# main.net
KiCad netlist of a schematic drawn in Altium Designer
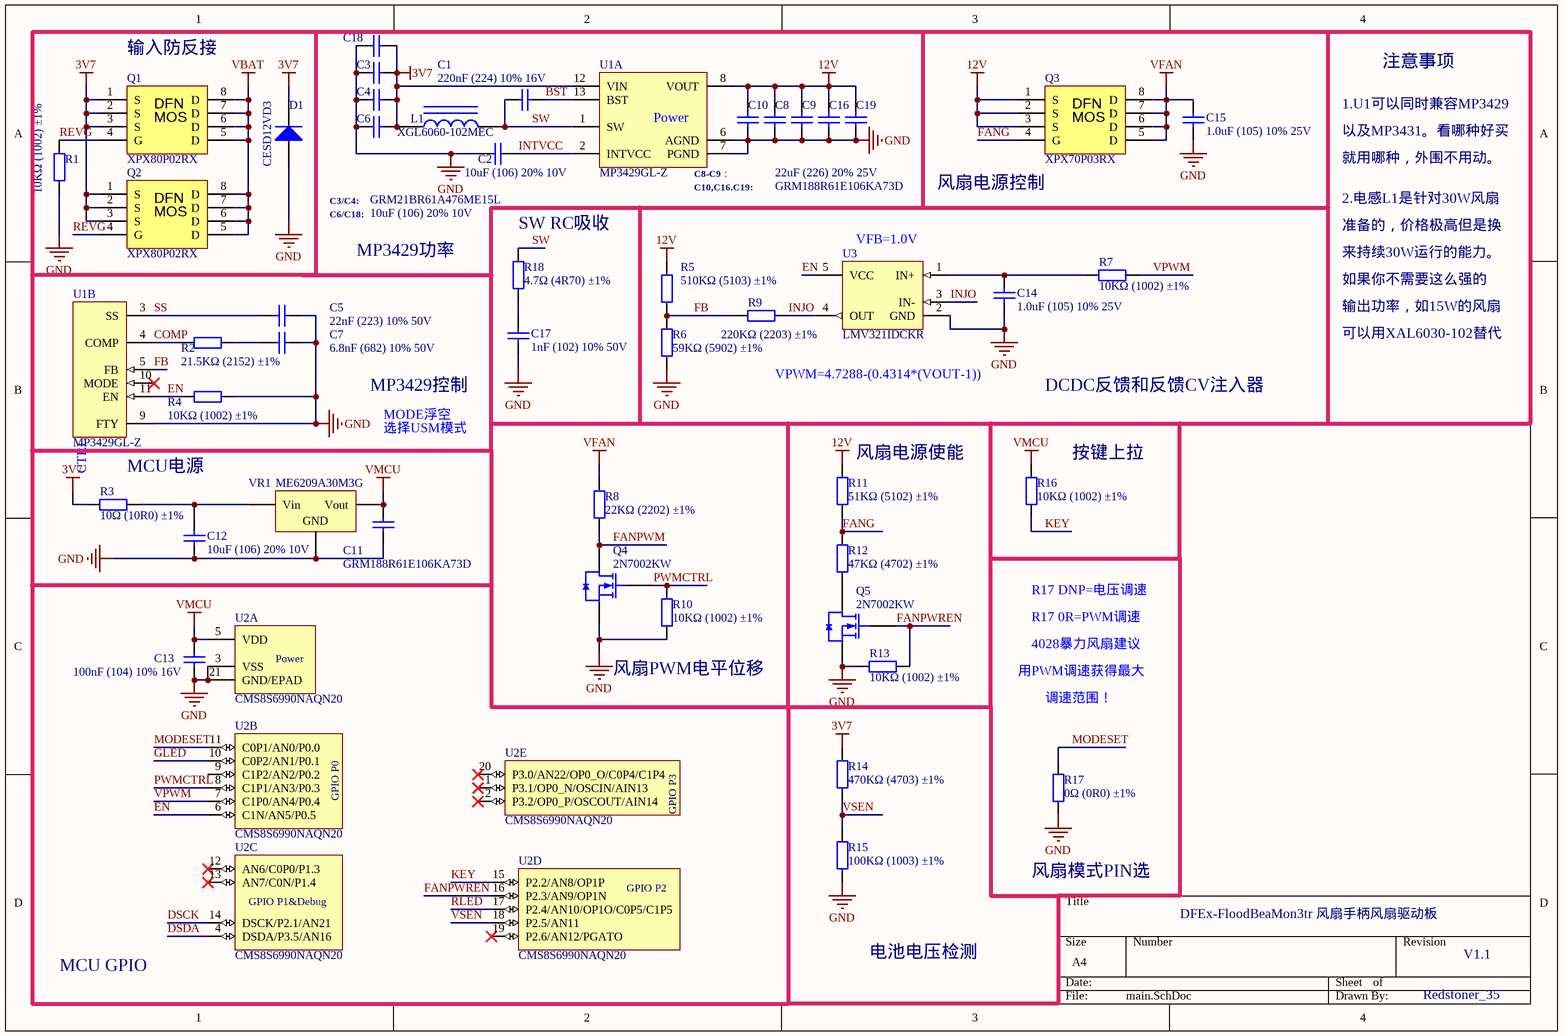
[diagram p0: main.SchDoc]

(export (version "E")
  (design (tool "Eeschema 10.0.6"))
  (components
    (comp (ref "C1")
      (value "220nF (224) 10% 16V")
      (footprint "0402_C")
      (description "贴片电容")
      (libsource (lib "Miscellaneous Devices LC") (part "0402 220nF (224) 10% 16V"))
    )
    (comp (ref "C2")
      (value "10uF (106) 20% 10V")
      (footprint "0402_C")
      (description "贴片电容")
      (libsource (lib "Miscellaneous Devices LC") (part "0402 10uF (106) 20% 6.3V"))
    )
    (comp (ref "C3")
      (value "GRM21BR61A476ME15L")
      (footprint "0805_C")
      (description "贴片MLCC电容，47uF (476) 20% 10V")
      (libsource (lib "Miscellaneous Devices LC") (part "0805 22uF (226) 20% 25V"))
    )
    (comp (ref "C4")
      (value "GRM21BR61A476ME15L")
      (footprint "0805_C")
      (description "贴片MLCC电容，47uF (476) 20% 10V")
      (libsource (lib "Miscellaneous Devices LC") (part "0805 22uF (226) 20% 25V"))
    )
    (comp (ref "C5")
      (value "22nF (223) 10% 50V")
      (footprint "0402_C")
      (description "贴片电容")
      (libsource (lib "Miscellaneous Devices LC") (part "0402 22nF (223) 10% 50V"))
    )
    (comp (ref "C6")
      (value "10uF (106) 20% 10V")
      (footprint "0402_C")
      (description "贴片电容")
      (libsource (lib "Miscellaneous Devices LC") (part "0402 10uF (106) 20% 6.3V"))
    )
    (comp (ref "C7")
      (value "6.8nF (682) 10% 50V")
      (footprint "0402_C")
      (description "贴片电容")
      (libsource (lib "Miscellaneous Devices LC") (part "0402 10nF (103) 10% 50V"))
    )
    (comp (ref "C8")
      (value "22uF (226) 20% 25V")
      (footprint "0805_C")
      (description "贴片电容")
      (libsource (lib "Miscellaneous Devices LC") (part "0805 22uF (226) 20% 25V"))
    )
    (comp (ref "C9")
      (value "22uF (226) 20% 25V")
      (footprint "0805_C")
      (description "贴片电容")
      (libsource (lib "Miscellaneous Devices LC") (part "0805 22uF (226) 20% 25V"))
    )
    (comp (ref "C10")
      (value "GRM188R61E106KA73D")
      (footprint "0603_C")
      (description "0603贴片MLCC电容 10uF ±20% 25V X5R")
      (libsource (lib "Miscellaneous Devices LC") (part "0603 4.7uF (475) 10% 16V"))
    )
    (comp (ref "C11")
      (value "GRM188R61E106KA73D")
      (footprint "0603_C")
      (description "0603贴片MLCC电容 10uF ±20% 25V X5R")
      (libsource (lib "Miscellaneous Devices LC") (part "0603 10uF (106) 10% 10V"))
    )
    (comp (ref "C12")
      (value "10uF (106) 20% 10V")
      (footprint "0402_C")
      (description "贴片电容")
      (libsource (lib "Miscellaneous Devices LC") (part "0402 10uF (106) 20% 6.3V"))
    )
    (comp (ref "C13")
      (value "100nF (104) 10% 16V")
      (footprint "0402_C")
      (description "贴片电容")
      (libsource (lib "Miscellaneous Devices LC") (part "0402 100nF (104) 10% 16V"))
    )
    (comp (ref "C14")
      (value "1.0uF (105) 10% 25V")
      (footprint "0402_C")
      (description "贴片电容")
      (libsource (lib "Miscellaneous Devices LC") (part "0402 1.0uF (105) 10% 25V"))
    )
    (comp (ref "C15")
      (value "1.0uF (105) 10% 25V")
      (footprint "0402_C")
      (description "贴片电容")
      (libsource (lib "Miscellaneous Devices LC") (part "0402 1.0uF (105) 10% 25V"))
    )
    (comp (ref "C16")
      (value "GRM188R61E106KA73D")
      (footprint "0603_C")
      (description "0603贴片MLCC电容 10uF ±20% 25V X5R")
      (libsource (lib "Miscellaneous Devices LC") (part "0603 4.7uF (475) 10% 16V"))
    )
    (comp (ref "C17")
      (value "1nF (102) 10% 50V")
      (footprint "0402_C")
      (description "贴片电容")
      (libsource (lib "Miscellaneous Devices LC") (part "0402 1nF (102) 10% 50V"))
    )
    (comp (ref "C18")
      (value "10uF (106) 20% 10V")
      (footprint "0402_C")
      (description "贴片电容")
      (libsource (lib "Miscellaneous Devices LC") (part "0402 10uF (106) 20% 6.3V"))
    )
    (comp (ref "C19")
      (value "GRM188R61E106KA73D")
      (footprint "0603_C")
      (description "0603贴片MLCC电容 10uF ±20% 25V X5R")
      (libsource (lib "Miscellaneous Devices LC") (part "0603 4.7uF (475) 10% 16V"))
    )
    (comp (ref "D1")
      (value "CESD12VD3")
      (footprint "SOD-323")
      (description "12V TVS二极管")
      (libsource (lib "Miscellaneous Devices LC") (part "SOD-323 1N4148WS T4"))
    )
    (comp (ref "L1")
      (value "XGL6060-102MEC")
      (footprint "XAL6030-xxxME")
      (description "线艺超低损耗系列一体成型电感 1.0uH±20% 2.5mΩ DCR 23A饱和电流 6.5*6.7*6.2mm")
      (fields (field (name "PUBLISHER") "Altium Limited"))
      (libsource (lib "Miscellaneous Devices") (part "Inductor Iron"))
    )
    (comp (ref "Q1")
      (value "XPX80P02RX")
      (footprint "DFN-8_L3.0-W3.0-P0.65-BL")
      (description "-20V -80A 4mR内阻 P沟道MOSFET")
      (libsource (lib "custom") (part "SON/DFN5x6 MOS"))
    )
    (comp (ref "Q2")
      (value "XPX80P02RX")
      (footprint "DFN-8_L3.0-W3.0-P0.65-BL")
      (description "-20V -80A 4mR内阻 P沟道MOSFET")
      (libsource (lib "custom") (part "SON/DFN5x6 MOS"))
    )
    (comp (ref "Q3")
      (value "XPX70P03RX")
      (footprint "DFN-8_L3.0-W3.0-P0.65-BL")
      (description "-30V -70A 6.5mR P沟道增强型MOSFET")
      (libsource (lib "custom") (part "SON/DFN5x6 MOS"))
    )
    (comp (ref "Q4")
      (value "2N7002KW")
      (footprint "SC70-3")
      (description "单N沟道MOSFET(场效应管)")
      (libsource (lib "Miscellaneous Devices LC") (part "2N7002 7002"))
    )
    (comp (ref "Q5")
      (value "2N7002KW")
      (footprint "SC70-3")
      (description "单N沟道MOSFET(场效应管)")
      (libsource (lib "Miscellaneous Devices LC") (part "2N7002 7002"))
    )
    (comp (ref "R1")
      (value "10KΩ (1002) ±1%")
      (footprint "0402_R")
      (description "贴片电阻")
      (libsource (lib "") (part "0402 10KΩ (1002) 1%_1"))
    )
    (comp (ref "R2")
      (value "21.5KΩ (2152) ±1%")
      (footprint "0402_R")
      (description "贴片电阻")
      (libsource (lib "Miscellaneous Devices LC") (part "0402 18KΩ (1802) 1%"))
    )
    (comp (ref "R3")
      (value "10Ω (10R0) ±1%")
      (footprint "0402_R")
      (description "贴片电阻")
      (libsource (lib "Miscellaneous Devices LC") (part "0402 22Ω (22R0) 1%"))
    )
    (comp (ref "R4")
      (value "10KΩ (1002) ±1%")
      (footprint "0402_R")
      (description "贴片电阻")
      (libsource (lib "Miscellaneous Devices LC") (part "0402 10KΩ (1002) 1%"))
    )
    (comp (ref "R5")
      (value "510KΩ (5103) ±1%")
      (footprint "0402_R")
      (description "贴片电阻")
      (libsource (lib "Miscellaneous Devices LC") (part "0402 510KΩ (5103) 1%"))
    )
    (comp (ref "R6")
      (value "59KΩ (5902) ±1%")
      (footprint "0402_R")
      (description "贴片电阻")
      (libsource (lib "Miscellaneous Devices LC") (part "0402 510KΩ (5103) 1%"))
    )
    (comp (ref "R7")
      (value "10KΩ (1002) ±1%")
      (footprint "0402_R")
      (description "贴片电阻")
      (libsource (lib "") (part "0402 10KΩ (1002) 1%_2"))
    )
    (comp (ref "R8")
      (value "22KΩ (2202) ±1%")
      (footprint "0402_R")
      (description "贴片电阻")
      (libsource (lib "Miscellaneous Devices LC") (part "0402 22KΩ (2202) 1%"))
    )
    (comp (ref "R9")
      (value "220KΩ (2203) ±1%")
      (footprint "0402_R")
      (description "贴片电阻")
      (libsource (lib "") (part "0402 100KΩ (1003) 1%_1"))
    )
    (comp (ref "R10")
      (value "10KΩ (1002) ±1%")
      (footprint "0402_R")
      (description "贴片电阻")
      (libsource (lib "") (part "0402 10KΩ (1002) 1%_1"))
    )
    (comp (ref "R11")
      (value "51KΩ (5102) ±1%")
      (footprint "0402_R")
      (description "贴片电阻")
      (libsource (lib "Miscellaneous Devices LC") (part "0402 47KΩ (4702) 1%"))
    )
    (comp (ref "R12")
      (value "47KΩ (4702) ±1%")
      (footprint "0402_R")
      (description "贴片电阻")
      (libsource (lib "Miscellaneous Devices LC") (part "0402 51KΩ (5102) 1%"))
    )
    (comp (ref "R13")
      (value "10KΩ (1002) ±1%")
      (footprint "0402_R")
      (description "贴片电阻")
      (libsource (lib "Miscellaneous Devices LC") (part "0402 10KΩ (1002) 1%"))
    )
    (comp (ref "R14")
      (value "470KΩ (4703) ±1%")
      (footprint "0402_R")
      (description "贴片电阻")
      (libsource (lib "Miscellaneous Devices LC") (part "0402 470KΩ (4703) 1%"))
    )
    (comp (ref "R15")
      (value "100KΩ (1003) ±1%")
      (footprint "0402_R")
      (description "贴片电阻")
      (libsource (lib "Miscellaneous Devices LC") (part "0402 100KΩ (1003) 1%"))
    )
    (comp (ref "R16")
      (value "10KΩ (1002) ±1%")
      (footprint "0402_R")
      (description "贴片电阻")
      (libsource (lib "") (part "0402 10KΩ (1002) 1%_1"))
    )
    (comp (ref "R17")
      (value "0Ω (0R0) ±1%")
      (footprint "0402_R")
      (description "贴片电阻")
      (libsource (lib "Miscellaneous Devices LC") (part "0402 0Ω (0R0) 1%"))
    )
    (comp (ref "R18")
      (value "4.7Ω (4R70) ±1%")
      (footprint "0402_R")
      (description "贴片电阻")
      (libsource (lib "Miscellaneous Devices LC") (part "0402 1Ω (1R00) 1%"))
    )
    (comp (ref "U1")
      (value "MP3429GL-Z")
      (footprint "QFN-MLP3*4-13L")
      (description "16VOUT, 21A Peak Current Fully Integrated Synchronous Boost Converter")
      (libsource (lib "") (part "MP3429GL-Z_1"))
    )
    (comp (ref "U2")
      (value "CMS8S6990NAQN20")
      (footprint "QFN40P300X300X800_HS-21N")
      (description "增强型闪存1T 8051单片机，16KB Flash 256+1K XRAM")
      (libsource (lib "custom") (part "CM8S6990NA-QFN20"))
    )
    (comp (ref "U3")
      (value "LMV321IDCKR")
      (footprint "SC70-5")
      (description "CMOS超小型运算放大器，SC70-5")
      (libsource (lib "custom") (part "LMV321IDCKR"))
    )
    (comp (ref "VR1")
      (value "ME6209A30M3G")
      (footprint "SOT-23-3L")
      (description "低压差线性稳压(LDO)，输入耐压18V 输出3V 300mA最大电流 SOT23-3封装")
      (libsource (lib "Miscellaneous Devices LC") (part "SOT-23 XC6206P332MR"))
    )
  )
  (nets
    (net (code "1") (name "/BST") (class "Default")
      (node (ref "C1") (pin "2") (pinfunction "2_2") (pintype "passive"))
      (node (ref "U1") (pin "13") (pinfunction "BST_13") (pintype "power_in"))
    )
    (net (code "2") (name "/COMP") (class "Default")
      (node (ref "R2") (pin "1") (pinfunction "1_1") (pintype "passive"))
      (node (ref "U1") (pin "4") (pinfunction "COMP_4") (pintype "passive"))
    )
    (net (code "3") (name "/DSCK") (class "Default")
      (node (ref "U2") (pin "14") (pinfunction "DSCK/P2.1/AN21_14") (pintype "bidirectional"))
    )
    (net (code "4") (name "/DSDA") (class "Default")
      (node (ref "U2") (pin "4") (pinfunction "DSDA/P3.5/AN16_4") (pintype "bidirectional"))
    )
    (net (code "5") (name "/EN") (class "Default")
      (node (ref "R4") (pin "2") (pinfunction "2_2") (pintype "passive"))
      (node (ref "U1") (pin "11") (pinfunction "EN_11") (pintype "input"))
      (node (ref "U2") (pin "6") (pinfunction "C1N/AN5/P0.5_6") (pintype "bidirectional"))
      (node (ref "U3") (pin "5") (pinfunction "VCC_5") (pintype "power_in"))
    )
    (net (code "6") (name "/FANG") (class "Default")
      (node (ref "Q3") (pin "4") (pinfunction "G_4") (pintype "passive"))
      (node (ref "R11") (pin "1") (pinfunction "1_1") (pintype "passive"))
      (node (ref "R12") (pin "2") (pinfunction "2_2") (pintype "passive"))
    )
    (net (code "7") (name "/FANPWM") (class "Default")
      (node (ref "Q4") (pin "3") (pinfunction "D_3") (pintype "passive"))
      (node (ref "R8") (pin "1") (pinfunction "1_1") (pintype "passive"))
    )
    (net (code "8") (name "/FANPWREN") (class "Default")
      (node (ref "Q5") (pin "1") (pinfunction "G_1") (pintype "passive"))
      (node (ref "R13") (pin "1") (pinfunction "1_1") (pintype "passive"))
      (node (ref "U2") (pin "16") (pinfunction "P2.3/AN9/OP1N_16") (pintype "bidirectional"))
    )
    (net (code "9") (name "/FB") (class "Default")
      (node (ref "R5") (pin "1") (pinfunction "1_1") (pintype "passive"))
      (node (ref "R6") (pin "2") (pinfunction "2_2") (pintype "passive"))
      (node (ref "R9") (pin "1") (pinfunction "1_1") (pintype "passive"))
      (node (ref "U1") (pin "5") (pinfunction "FB_5") (pintype "input"))
    )
    (net (code "10") (name "/GLED") (class "Default")
      (node (ref "U2") (pin "10") (pinfunction "C0P2/AN1/P0.1_10") (pintype "bidirectional"))
    )
    (net (code "11") (name "/INJO") (class "Default")
      (node (ref "R9") (pin "2") (pinfunction "2_2") (pintype "passive"))
      (node (ref "U3") (pin "3") (pinfunction "IN-_3") (pintype "input"))
      (node (ref "U3") (pin "4") (pinfunction "OUT_4") (pintype "output"))
    )
    (net (code "12") (name "/INTVCC") (class "Default")
      (node (ref "C2") (pin "2") (pinfunction "2_2") (pintype "passive"))
      (node (ref "U1") (pin "2") (pinfunction "INTVCC_2") (pintype "power_in"))
    )
    (net (code "13") (name "/KEY") (class "Default")
      (node (ref "R16") (pin "1") (pinfunction "1_1") (pintype "passive"))
      (node (ref "U2") (pin "15") (pinfunction "P2.2/AN8/OP1P_15") (pintype "bidirectional"))
    )
    (net (code "14") (name "/MODESET") (class "Default")
      (node (ref "R17") (pin "2") (pinfunction "2_2") (pintype "passive"))
      (node (ref "U2") (pin "11") (pinfunction "C0P1/AN0/P0.0_11") (pintype "bidirectional"))
    )
    (net (code "15") (name "/PWMCTRL") (class "Default")
      (node (ref "Q4") (pin "1") (pinfunction "G_1") (pintype "passive"))
      (node (ref "R10") (pin "2") (pinfunction "2_2") (pintype "passive"))
      (node (ref "U2") (pin "8") (pinfunction "C1P1/AN3/P0.3_8") (pintype "bidirectional"))
    )
    (net (code "16") (name "/REVG") (class "Default")
      (node (ref "Q1") (pin "4") (pinfunction "G_4") (pintype "passive"))
      (node (ref "Q2") (pin "4") (pinfunction "G_4") (pintype "passive"))
      (node (ref "R1") (pin "2") (pinfunction "2_2") (pintype "passive"))
    )
    (net (code "17") (name "/RLED") (class "Default")
      (node (ref "U2") (pin "17") (pinfunction "P2.4/AN10/OP1O/C0P5/C1P5_17") (pintype "bidirectional"))
    )
    (net (code "18") (name "/SS") (class "Default")
      (node (ref "C5") (pin "1") (pinfunction "1_1") (pintype "passive"))
      (node (ref "U1") (pin "3") (pinfunction "SS_3") (pintype "passive"))
    )
    (net (code "19") (name "/SW") (class "Default")
      (node (ref "C1") (pin "1") (pinfunction "1_1") (pintype "passive"))
      (node (ref "L1") (pin "2") (pinfunction "2_2") (pintype "passive"))
      (node (ref "R18") (pin "2") (pinfunction "2_2") (pintype "passive"))
      (node (ref "U1") (pin "1") (pinfunction "SW_1") (pintype "power_in"))
    )
    (net (code "20") (name "/VPWM") (class "Default")
      (node (ref "R7") (pin "2") (pinfunction "2_2") (pintype "passive"))
      (node (ref "U2") (pin "7") (pinfunction "C1P0/AN4/P0.4_7") (pintype "bidirectional"))
    )
    (net (code "21") (name "/VSEN") (class "Default")
      (node (ref "R14") (pin "1") (pinfunction "1_1") (pintype "passive"))
      (node (ref "R15") (pin "2") (pinfunction "2_2") (pintype "passive"))
      (node (ref "U2") (pin "18") (pinfunction "P2.5/AN11_18") (pintype "bidirectional"))
    )
    (net (code "22") (name "3V7") (class "Default")
      (node (ref "C18") (pin "2") (pinfunction "2_2") (pintype "passive"))
      (node (ref "C3") (pin "2") (pinfunction "2_2") (pintype "passive"))
      (node (ref "C4") (pin "2") (pinfunction "2_2") (pintype "passive"))
      (node (ref "C6") (pin "2") (pinfunction "2_2") (pintype "passive"))
      (node (ref "D1") (pin "2") (pinfunction "K_2") (pintype "passive"))
      (node (ref "L1") (pin "1") (pinfunction "1_1") (pintype "passive"))
      (node (ref "Q1") (pin "1") (pinfunction "S_1") (pintype "passive"))
      (node (ref "Q1") (pin "2") (pinfunction "S_2") (pintype "passive"))
      (node (ref "Q1") (pin "3") (pinfunction "S_3") (pintype "passive"))
      (node (ref "Q2") (pin "1") (pinfunction "S_1") (pintype "passive"))
      (node (ref "Q2") (pin "2") (pinfunction "S_2") (pintype "passive"))
      (node (ref "Q2") (pin "3") (pinfunction "S_3") (pintype "passive"))
      (node (ref "R14") (pin "2") (pinfunction "2_2") (pintype "passive"))
      (node (ref "R3") (pin "1") (pinfunction "1_1") (pintype "passive"))
      (node (ref "U1") (pin "12") (pinfunction "VIN_12") (pintype "power_in"))
    )
    (net (code "23") (name "12V") (class "Default")
      (node (ref "C10") (pin "2") (pinfunction "2_2") (pintype "passive"))
      (node (ref "C16") (pin "2") (pinfunction "2_2") (pintype "passive"))
      (node (ref "C19") (pin "2") (pinfunction "2_2") (pintype "passive"))
      (node (ref "C8") (pin "2") (pinfunction "2_2") (pintype "passive"))
      (node (ref "C9") (pin "2") (pinfunction "2_2") (pintype "passive"))
      (node (ref "Q3") (pin "1") (pinfunction "S_1") (pintype "passive"))
      (node (ref "Q3") (pin "2") (pinfunction "S_2") (pintype "passive"))
      (node (ref "Q3") (pin "3") (pinfunction "S_3") (pintype "passive"))
      (node (ref "R11") (pin "2") (pinfunction "2_2") (pintype "passive"))
      (node (ref "R5") (pin "2") (pinfunction "2_2") (pintype "passive"))
      (node (ref "U1") (pin "8") (pinfunction "VOUT_8") (pintype "power_in"))
    )
    (net (code "24") (name "GND") (class "Default")
      (node (ref "C10") (pin "1") (pinfunction "1_1") (pintype "passive"))
      (node (ref "C11") (pin "1") (pinfunction "1_1") (pintype "passive"))
      (node (ref "C12") (pin "1") (pinfunction "1_1") (pintype "passive"))
      (node (ref "C13") (pin "1") (pinfunction "1_1") (pintype "passive"))
      (node (ref "C14") (pin "1") (pinfunction "1_1") (pintype "passive"))
      (node (ref "C15") (pin "1") (pinfunction "1_1") (pintype "passive"))
      (node (ref "C16") (pin "1") (pinfunction "1_1") (pintype "passive"))
      (node (ref "C17") (pin "1") (pinfunction "1_1") (pintype "passive"))
      (node (ref "C18") (pin "1") (pinfunction "1_1") (pintype "passive"))
      (node (ref "C19") (pin "1") (pinfunction "1_1") (pintype "passive"))
      (node (ref "C2") (pin "1") (pinfunction "1_1") (pintype "passive"))
      (node (ref "C3") (pin "1") (pinfunction "1_1") (pintype "passive"))
      (node (ref "C4") (pin "1") (pinfunction "1_1") (pintype "passive"))
      (node (ref "C5") (pin "2") (pinfunction "2_2") (pintype "passive"))
      (node (ref "C6") (pin "1") (pinfunction "1_1") (pintype "passive"))
      (node (ref "C7") (pin "2") (pinfunction "2_2") (pintype "passive"))
      (node (ref "C8") (pin "1") (pinfunction "1_1") (pintype "passive"))
      (node (ref "C9") (pin "1") (pinfunction "1_1") (pintype "passive"))
      (node (ref "D1") (pin "1") (pinfunction "A_1") (pintype "passive"))
      (node (ref "Q4") (pin "2") (pinfunction "S_2") (pintype "passive"))
      (node (ref "Q5") (pin "2") (pinfunction "S_2") (pintype "passive"))
      (node (ref "R1") (pin "1") (pinfunction "1_1") (pintype "passive"))
      (node (ref "R10") (pin "1") (pinfunction "1_1") (pintype "passive"))
      (node (ref "R13") (pin "2") (pinfunction "2_2") (pintype "passive"))
      (node (ref "R15") (pin "1") (pinfunction "1_1") (pintype "passive"))
      (node (ref "R17") (pin "1") (pinfunction "1_1") (pintype "passive"))
      (node (ref "R4") (pin "1") (pinfunction "1_1") (pintype "passive"))
      (node (ref "R6") (pin "1") (pinfunction "1_1") (pintype "passive"))
      (node (ref "U1") (pin "6") (pinfunction "AGND_6") (pintype "power_in"))
      (node (ref "U1") (pin "7") (pinfunction "PGND_7") (pintype "power_in"))
      (node (ref "U1") (pin "9") (pinfunction "FTY_9") (pintype "passive"))
      (node (ref "U2") (pin "21") (pinfunction "GND/EPAD_21") (pintype "power_in"))
      (node (ref "U2") (pin "3") (pinfunction "VSS_3") (pintype "power_in"))
      (node (ref "U3") (pin "2") (pinfunction "GND_2") (pintype "power_in"))
      (node (ref "VR1") (pin "1") (pinfunction "GND_1") (pintype "passive"))
    )
    (net (code "25") (name "Net-(C7-Pad1)") (class "Default")
      (node (ref "C7") (pin "1") (pinfunction "1_1") (pintype "passive"))
      (node (ref "R2") (pin "2") (pinfunction "2_2") (pintype "passive"))
    )
    (net (code "26") (name "Net-(C17-Pad2)") (class "Default")
      (node (ref "C17") (pin "2") (pinfunction "2_2") (pintype "passive"))
      (node (ref "R18") (pin "1") (pinfunction "1_1") (pintype "passive"))
    )
    (net (code "27") (name "Net-(Q5-D)") (class "Default")
      (node (ref "Q5") (pin "3") (pinfunction "D_3") (pintype "passive"))
      (node (ref "R12") (pin "1") (pinfunction "1_1") (pintype "passive"))
    )
    (net (code "28") (name "Net-(U3-IN+)") (class "Default")
      (node (ref "C14") (pin "2") (pinfunction "2_2") (pintype "passive"))
      (node (ref "R7") (pin "1") (pinfunction "1_1") (pintype "passive"))
      (node (ref "U3") (pin "1") (pinfunction "IN+_1") (pintype "input"))
    )
    (net (code "29") (name "Net-(VR1-Vin)") (class "Default")
      (node (ref "C12") (pin "2") (pinfunction "2_2") (pintype "passive"))
      (node (ref "R3") (pin "2") (pinfunction "2_2") (pintype "passive"))
      (node (ref "VR1") (pin "3") (pinfunction "Vin_3") (pintype "passive"))
    )
    (net (code "30") (name "VBAT") (class "Default")
      (node (ref "Q1") (pin "5") (pinfunction "D_5") (pintype "passive"))
      (node (ref "Q1") (pin "6") (pinfunction "D_6") (pintype "passive"))
      (node (ref "Q1") (pin "7") (pinfunction "D_7") (pintype "passive"))
      (node (ref "Q1") (pin "8") (pinfunction "D_8") (pintype "passive"))
      (node (ref "Q2") (pin "5") (pinfunction "D_5") (pintype "passive"))
      (node (ref "Q2") (pin "6") (pinfunction "D_6") (pintype "passive"))
      (node (ref "Q2") (pin "7") (pinfunction "D_7") (pintype "passive"))
      (node (ref "Q2") (pin "8") (pinfunction "D_8") (pintype "passive"))
    )
    (net (code "31") (name "VFAN") (class "Default")
      (node (ref "C15") (pin "2") (pinfunction "2_2") (pintype "passive"))
      (node (ref "Q3") (pin "5") (pinfunction "D_5") (pintype "passive"))
      (node (ref "Q3") (pin "6") (pinfunction "D_6") (pintype "passive"))
      (node (ref "Q3") (pin "7") (pinfunction "D_7") (pintype "passive"))
      (node (ref "Q3") (pin "8") (pinfunction "D_8") (pintype "passive"))
      (node (ref "R8") (pin "2") (pinfunction "2_2") (pintype "passive"))
    )
    (net (code "32") (name "VMCU") (class "Default")
      (node (ref "C11") (pin "2") (pinfunction "2_2") (pintype "passive"))
      (node (ref "C13") (pin "2") (pinfunction "2_2") (pintype "passive"))
      (node (ref "R16") (pin "2") (pinfunction "2_2") (pintype "passive"))
      (node (ref "U2") (pin "5") (pinfunction "VDD_5") (pintype "power_in"))
      (node (ref "VR1") (pin "2") (pinfunction "Vout_2") (pintype "passive"))
    )
    (net (code "33") (name "unconnected-(U1B-MODE-Pad10)") (class "Default")
      (node (ref "U1") (pin "10") (pinfunction "MODE_10") (pintype "input+no_connect"))
    )
    (net (code "34") (name "unconnected-(U2B-C1P2{slash}AN2{slash}P0.2-Pad9)") (class "Default")
      (node (ref "U2") (pin "9") (pinfunction "C1P2/AN2/P0.2_9") (pintype "bidirectional"))
    )
    (net (code "35") (name "unconnected-(U2C-AN6{slash}C0P0{slash}P1.3-Pad12)") (class "Default")
      (node (ref "U2") (pin "12") (pinfunction "AN6/C0P0/P1.3_12") (pintype "bidirectional+no_connect"))
    )
    (net (code "36") (name "unconnected-(U2C-AN7{slash}C0N{slash}P1.4-Pad13)") (class "Default")
      (node (ref "U2") (pin "13") (pinfunction "AN7/C0N/P1.4_13") (pintype "bidirectional+no_connect"))
    )
    (net (code "37") (name "unconnected-(U2D-P2.6{slash}AN12{slash}PGATO-Pad19)") (class "Default")
      (node (ref "U2") (pin "19") (pinfunction "P2.6/AN12/PGATO_19") (pintype "bidirectional+no_connect"))
    )
    (net (code "38") (name "unconnected-(U2E-P3.0{slash}AN22{slash}OP0_O{slash}C0P4{slash}C1P4-Pad20)") (class "Default")
      (node (ref "U2") (pin "20") (pinfunction "P3.0/AN22/OP0_O/C0P4/C1P4_20") (pintype "bidirectional+no_connect"))
    )
    (net (code "39") (name "unconnected-(U2E-P3.1{slash}OP0_N{slash}OSCIN{slash}AIN13-Pad1)") (class "Default")
      (node (ref "U2") (pin "1") (pinfunction "P3.1/OP0_N/OSCIN/AIN13_1") (pintype "bidirectional+no_connect"))
    )
    (net (code "40") (name "unconnected-(U2E-P3.2{slash}OP0_P{slash}OSCOUT{slash}AIN14-Pad2)") (class "Default")
      (node (ref "U2") (pin "2") (pinfunction "P3.2/OP0_P/OSCOUT/AIN14_2") (pintype "bidirectional+no_connect"))
    )
  )
)
